# 468332_001_Inputs.net
KiCad netlist of a schematic drawn in Altium Designer
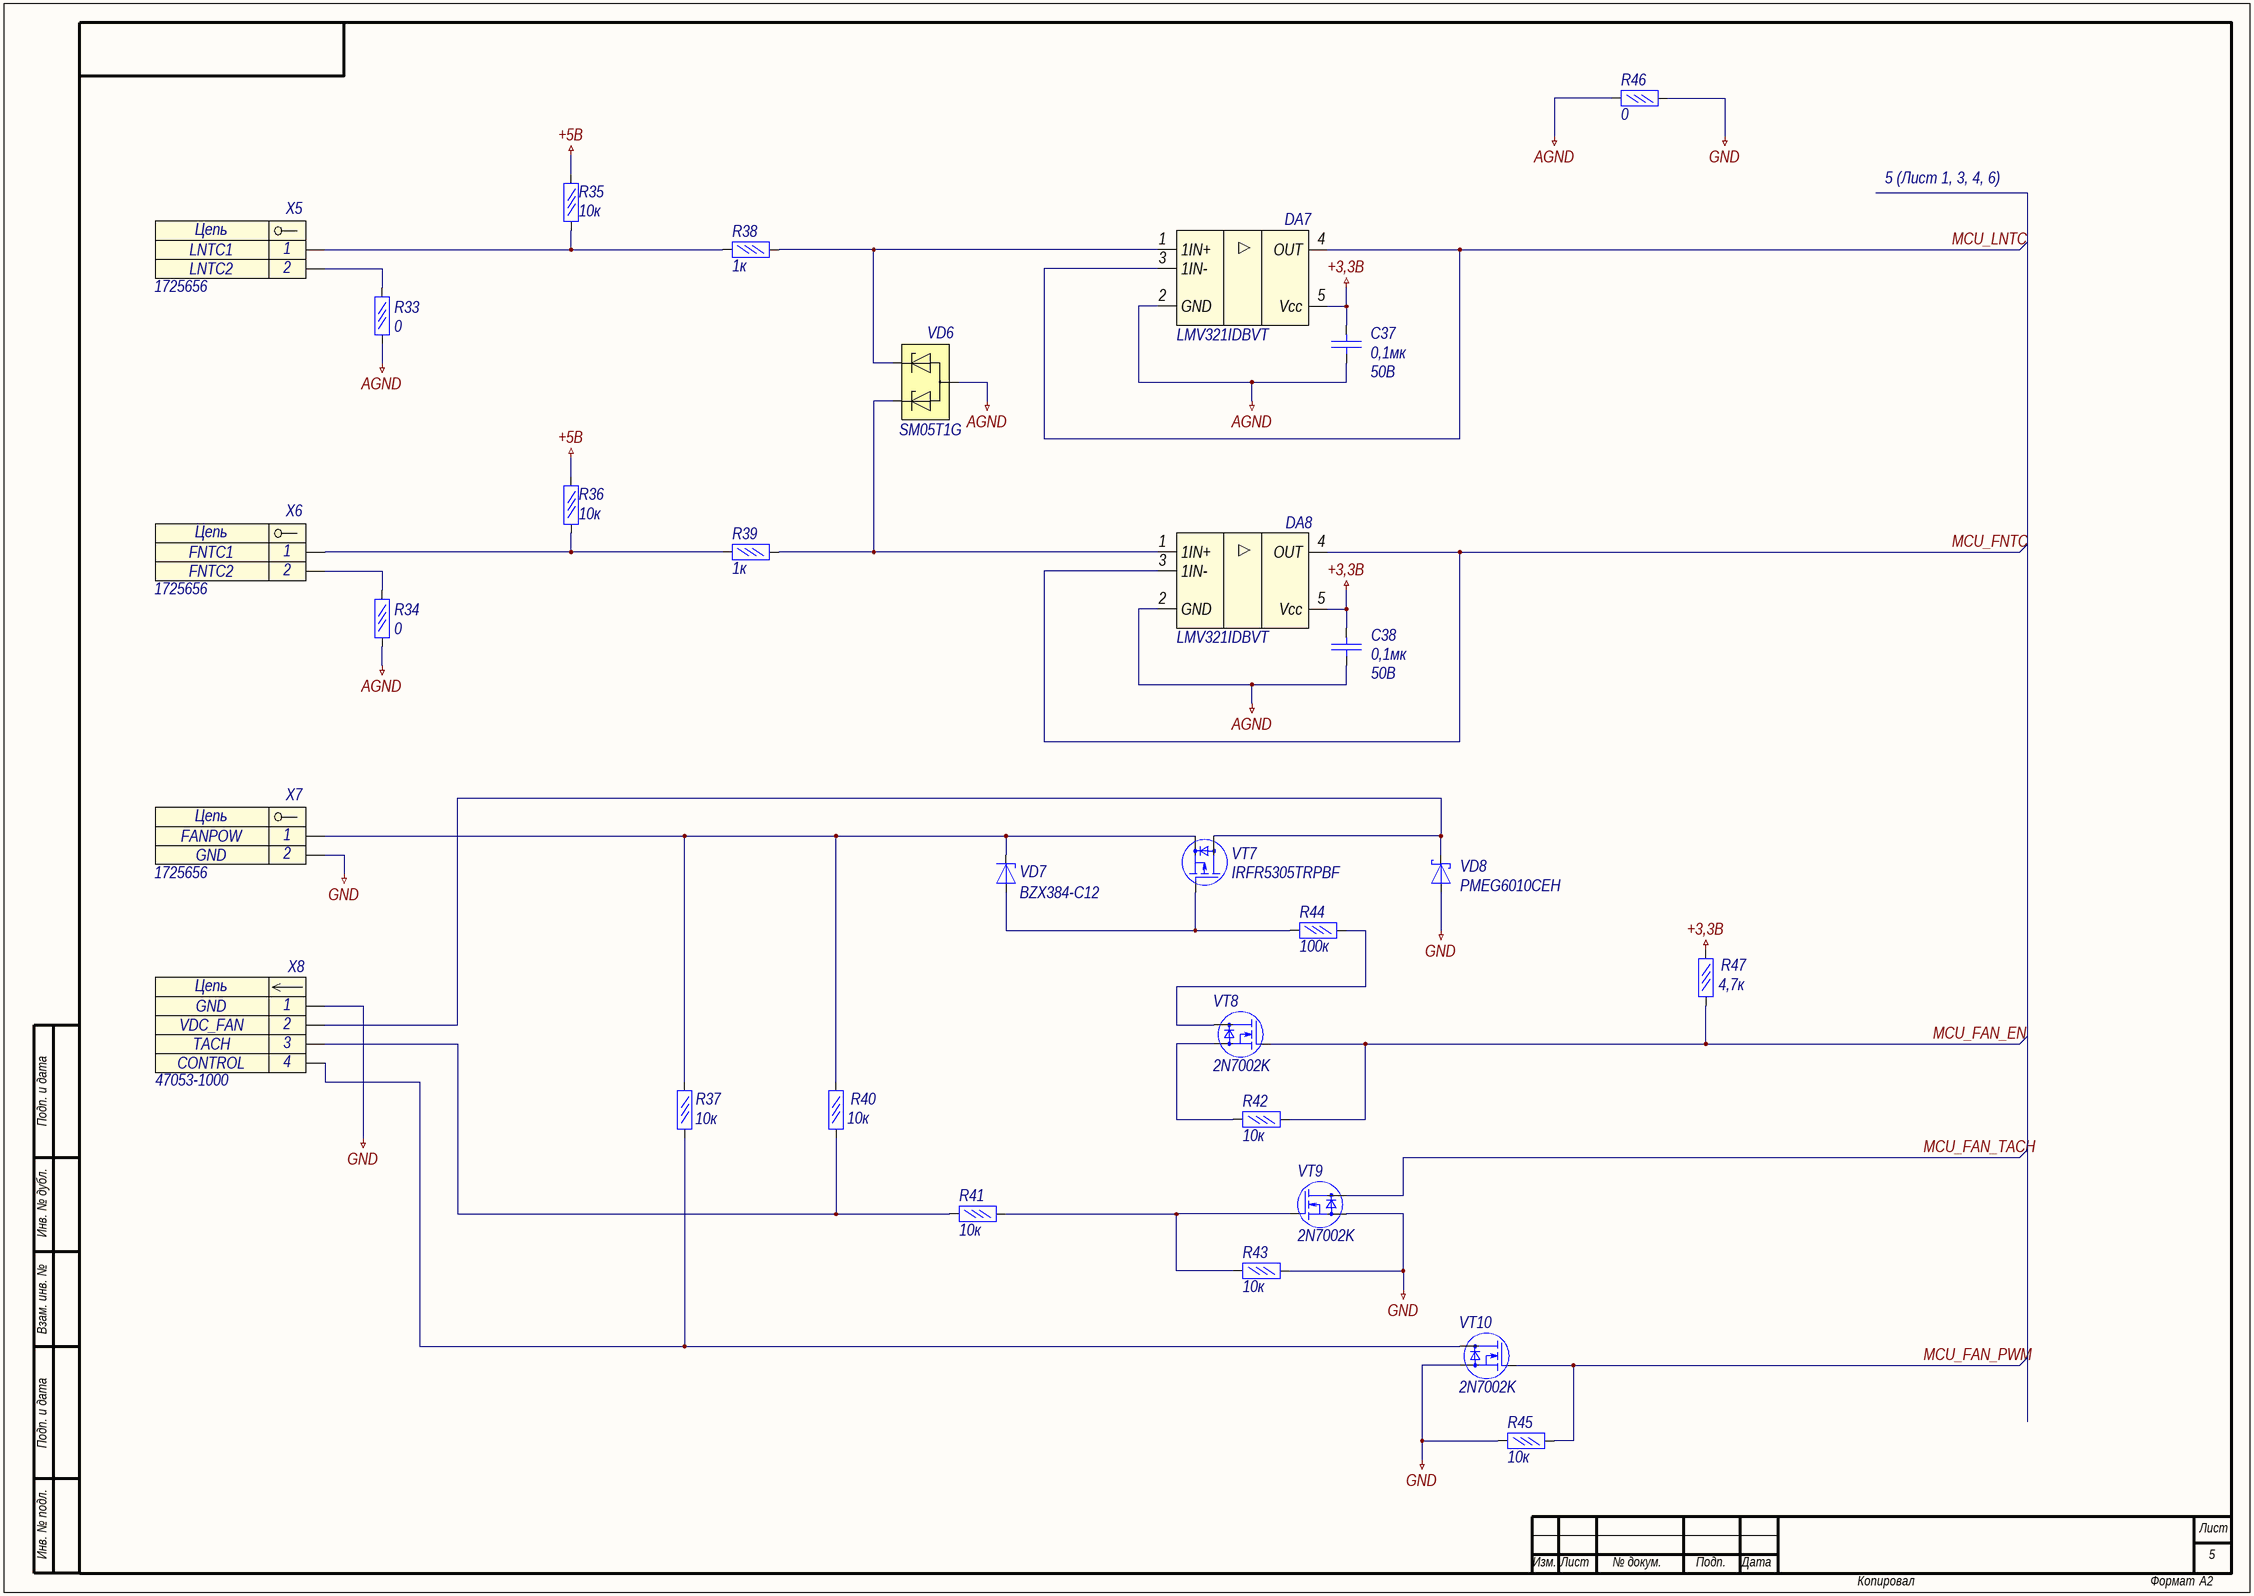
[diagram p0: РЕУН.468332.001_Inputs.SchDoc]

(export (version "E")
  (design (tool "Eeschema 10.0.6"))
  (components
    (comp (ref "C37")
      (value "0,1мк")
      (footprint "C0805_AA")
      (description "Конденсатор кер.")
      (fields (field (name "VOLTAGE") "50В"))
      (libsource (lib "Library_Diana") (part "Конденсатор кер."))
    )
    (comp (ref "C38")
      (value "0,1мк")
      (footprint "C0805_AA")
      (description "Конденсатор кер.")
      (fields (field (name "VOLTAGE") "50В"))
      (libsource (lib "Library_Diana") (part "Конденсатор кер."))
    )
    (comp (ref "DA7")
      (value "LMV321IDBVT")
      (description "Операционный усилитель Rail-to-rail")
      (libsource (lib "Library_Diana") (part "LMV321"))
    )
    (comp (ref "DA8")
      (value "LMV321IDBVT")
      (description "Операционный усилитель Rail-to-rail")
      (libsource (lib "Library_Diana") (part "LMV321"))
    )
    (comp (ref "R33")
      (value "0")
      (footprint "R1206")
      (description "Резистор 0,05Вт")
      (libsource (lib "Library_Diana") (part "Резистор  0,05Вт"))
    )
    (comp (ref "R34")
      (value "0")
      (footprint "R1206")
      (description "Резистор 0,05Вт")
      (libsource (lib "Library_Diana") (part "Резистор  0,05Вт"))
    )
    (comp (ref "R35")
      (value "10к")
      (footprint "R1206")
      (description "Резистор 0,05Вт")
      (libsource (lib "Library_Diana") (part "Резистор  0,05Вт"))
    )
    (comp (ref "R36")
      (value "10к")
      (footprint "R1206")
      (description "Резистор 0,05Вт")
      (libsource (lib "Library_Diana") (part "Резистор  0,05Вт"))
    )
    (comp (ref "R37")
      (value "10к")
      (footprint "R1206")
      (description "Резистор 0,05Вт")
      (libsource (lib "Library_Diana") (part "Резистор  0,05Вт"))
    )
    (comp (ref "R38")
      (value "1к")
      (footprint "R1206")
      (description "Резистор 0,05Вт")
      (libsource (lib "") (part "Резистор  0,05Вт_2"))
    )
    (comp (ref "R39")
      (value "1к")
      (footprint "R1206")
      (description "Резистор 0,05Вт")
      (libsource (lib "") (part "Резистор  0,05Вт_2"))
    )
    (comp (ref "R40")
      (value "10к")
      (footprint "R1206")
      (description "Резистор 0,05Вт")
      (libsource (lib "Library_Diana") (part "Резистор  0,05Вт"))
    )
    (comp (ref "R41")
      (value "10к")
      (footprint "R1206")
      (description "Резистор 0,05Вт")
      (libsource (lib "") (part "Резистор  0,05Вт_2"))
    )
    (comp (ref "R42")
      (value "10к")
      (footprint "R1206")
      (description "Резистор 0,05Вт")
      (libsource (lib "") (part "Резистор  0,05Вт_1"))
    )
    (comp (ref "R43")
      (value "10к")
      (footprint "R1206")
      (description "Резистор 0,05Вт")
      (libsource (lib "") (part "Резистор  0,05Вт_1"))
    )
    (comp (ref "R44")
      (value "100к")
      (footprint "R1206")
      (description "Резистор 0,05Вт")
      (libsource (lib "") (part "Резистор  0,05Вт_2"))
    )
    (comp (ref "R45")
      (value "10к")
      (footprint "R1206")
      (description "Резистор 0,05Вт")
      (libsource (lib "") (part "Резистор  0,05Вт_1"))
    )
    (comp (ref "R46")
      (value "0")
      (footprint "R1206")
      (description "Резистор 0,05Вт")
      (libsource (lib "") (part "Резистор  0,05Вт_1"))
    )
    (comp (ref "R47")
      (value "4,7к")
      (footprint "R1206")
      (description "Резистор 0,05Вт")
      (libsource (lib "Library_Diana") (part "Резистор  0,05Вт"))
    )
    (comp (ref "VD6")
      (value "SM05T1G")
      (description "Сборка TVS-диодов")
      (libsource (lib "Library_Diana") (part "ZenerArray2"))
    )
    (comp (ref "VD7")
      (value "BZX384-C12")
      (footprint "SOT23-2_A")
      (description "Стабилитрон")
      (libsource (lib "Library_Diana") (part "DiodeZener"))
    )
    (comp (ref "VD8")
      (value "PMEG6010CEH")
      (footprint "SOD123_A")
      (description "Диод Шоттки")
      (libsource (lib "Library_Diana") (part "DiodeSchottky"))
    )
    (comp (ref "VT7")
      (value "IRFR5305TRPBF")
      (description "Полевой P-канальный транзистор")
      (fields (field (name "NAME") "IRFR5305TRPBF"))
      (libsource (lib "Library_Diana") (part "mosfet-p-1-3-2"))
    )
    (comp (ref "VT8")
      (value "2N7002K")
      (footprint "SOT:SOT23-3")
      (fields (field (name "NAME") "2N7002K"))
      (libsource (lib "Library_Diana") (part "mosfet-n"))
    )
    (comp (ref "VT9")
      (value "2N7002K")
      (footprint "SOT:SOT23-3")
      (fields (field (name "NAME") "2N7002K"))
      (libsource (lib "Library_Diana") (part "mosfet-n"))
    )
    (comp (ref "VT10")
      (value "2N7002K")
      (footprint "SOT:SOT23-3")
      (fields (field (name "NAME") "2N7002K"))
      (libsource (lib "Library_Diana") (part "mosfet-n"))
    )
    (comp (ref "X5")
      (value "1725656")
      (description "Разъем - 1 конт. клемма")
      (fields (field (name "NAME") "1725656"))
      (libsource (lib "Library_Diana") (part "x1-k_1"))
    )
    (comp (ref "X6")
      (value "1725656")
      (description "Разъем - 1 конт. клемма")
      (fields (field (name "NAME") "1725656"))
      (libsource (lib "Library_Diana") (part "x1-k_1"))
    )
    (comp (ref "X7")
      (value "1725656")
      (description "Разъем - 1 конт. клемма")
      (fields (field (name "NAME") "1725656"))
      (libsource (lib "Library_Diana") (part "x1-k_1"))
    )
    (comp (ref "X8")
      (value "47053-1000")
      (description "Разъем - 10 конт. вилка")
      (fields (field (name "NAME") "47053-1000"))
      (libsource (lib "Library_Diana") (part "x10-m_1"))
    )
  )
  (nets
    (net (code "1") (name "+3,3В") (class "Default")
      (node (ref "C37") (pin "2") (pinfunction "2_2") (pintype "passive"))
      (node (ref "C38") (pin "2") (pinfunction "2_2") (pintype "passive"))
      (node (ref "DA7") (pin "5") (pinfunction "Vcc_5") (pintype "passive"))
      (node (ref "DA8") (pin "5") (pinfunction "Vcc_5") (pintype "passive"))
      (node (ref "R47") (pin "2") (pinfunction "2_2") (pintype "passive"))
    )
    (net (code "2") (name "+5В") (class "Default")
      (node (ref "R35") (pin "2") (pinfunction "2_2") (pintype "passive"))
      (node (ref "R36") (pin "2") (pinfunction "2_2") (pintype "passive"))
    )
    (net (code "3") (name "/MCU_FAN_EN") (class "Default")
      (node (ref "R42") (pin "1") (pinfunction "1_1") (pintype "passive"))
      (node (ref "R47") (pin "1") (pinfunction "1_1") (pintype "passive"))
      (node (ref "VT8") (pin "1") (pinfunction "G_1") (pintype "passive"))
    )
    (net (code "4") (name "/MCU_FAN_PWM") (class "Default")
      (node (ref "R45") (pin "1") (pinfunction "1_1") (pintype "passive"))
      (node (ref "VT10") (pin "1") (pinfunction "G_1") (pintype "passive"))
    )
    (net (code "5") (name "/MCU_FAN_TACH") (class "Default")
      (node (ref "VT9") (pin "3") (pinfunction "D_3") (pintype "passive"))
    )
    (net (code "6") (name "/MCU_FNTC") (class "Default")
      (node (ref "DA8") (pin "3") (pinfunction "1IN-_3") (pintype "passive"))
      (node (ref "DA8") (pin "4") (pinfunction "OUT_4") (pintype "passive"))
    )
    (net (code "7") (name "/MCU_LNTC") (class "Default")
      (node (ref "DA7") (pin "3") (pinfunction "1IN-_3") (pintype "passive"))
      (node (ref "DA7") (pin "4") (pinfunction "OUT_4") (pintype "passive"))
    )
    (net (code "8") (name "AGND") (class "Default")
      (node (ref "C37") (pin "1") (pinfunction "1_1") (pintype "passive"))
      (node (ref "C38") (pin "1") (pinfunction "1_1") (pintype "passive"))
      (node (ref "DA7") (pin "2") (pinfunction "GND_2") (pintype "passive"))
      (node (ref "DA8") (pin "2") (pinfunction "GND_2") (pintype "passive"))
      (node (ref "R33") (pin "1") (pinfunction "1_1") (pintype "passive"))
      (node (ref "R34") (pin "1") (pinfunction "1_1") (pintype "passive"))
      (node (ref "R46") (pin "2") (pinfunction "2_2") (pintype "passive"))
      (node (ref "VD6") (pin "3") (pintype "passive"))
    )
    (net (code "9") (name "GND") (class "Default")
      (node (ref "R43") (pin "1") (pinfunction "1_1") (pintype "passive"))
      (node (ref "R45") (pin "2") (pinfunction "2_2") (pintype "passive"))
      (node (ref "R46") (pin "1") (pinfunction "1_1") (pintype "passive"))
      (node (ref "VD8") (pin "2") (pinfunction "A_2") (pintype "passive"))
      (node (ref "VT10") (pin "2") (pinfunction "S_2") (pintype "passive"))
      (node (ref "VT9") (pin "2") (pinfunction "S_2") (pintype "passive"))
      (node (ref "X7") (pin "2") (pinfunction "2_2") (pintype "passive"))
      (node (ref "X8") (pin "1") (pinfunction "1_1") (pintype "passive"))
    )
    (net (code "10") (name "Net-(DA7-1IN+)") (class "Default")
      (node (ref "DA7") (pin "1") (pinfunction "1IN+_1") (pintype "passive"))
      (node (ref "R38") (pin "2") (pinfunction "2_2") (pintype "passive"))
      (node (ref "VD6") (pin "2") (pintype "passive"))
    )
    (net (code "11") (name "Net-(DA8-1IN+)") (class "Default")
      (node (ref "DA8") (pin "1") (pinfunction "1IN+_1") (pintype "passive"))
      (node (ref "R39") (pin "2") (pinfunction "2_2") (pintype "passive"))
      (node (ref "VD6") (pin "1") (pintype "passive"))
    )
    (net (code "12") (name "Net-(R33-Pad2)") (class "Default")
      (node (ref "R33") (pin "2") (pinfunction "2_2") (pintype "passive"))
      (node (ref "X5") (pin "2") (pinfunction "2_2") (pintype "passive"))
    )
    (net (code "13") (name "Net-(R34-Pad2)") (class "Default")
      (node (ref "R34") (pin "2") (pinfunction "2_2") (pintype "passive"))
      (node (ref "X6") (pin "2") (pinfunction "2_2") (pintype "passive"))
    )
    (net (code "14") (name "Net-(R35-Pad1)") (class "Default")
      (node (ref "R35") (pin "1") (pinfunction "1_1") (pintype "passive"))
      (node (ref "R38") (pin "1") (pinfunction "1_1") (pintype "passive"))
      (node (ref "X5") (pin "1") (pinfunction "1_1") (pintype "passive"))
    )
    (net (code "15") (name "Net-(R36-Pad1)") (class "Default")
      (node (ref "R36") (pin "1") (pinfunction "1_1") (pintype "passive"))
      (node (ref "R39") (pin "1") (pinfunction "1_1") (pintype "passive"))
      (node (ref "X6") (pin "1") (pinfunction "1_1") (pintype "passive"))
    )
    (net (code "16") (name "Net-(R40-Pad1)") (class "Default")
      (node (ref "R40") (pin "1") (pinfunction "1_1") (pintype "passive"))
      (node (ref "R41") (pin "1") (pinfunction "1_1") (pintype "passive"))
      (node (ref "X8") (pin "3") (pinfunction "3_3") (pintype "passive"))
    )
    (net (code "17") (name "Net-(VD7-A)") (class "Default")
      (node (ref "R44") (pin "1") (pinfunction "1_1") (pintype "passive"))
      (node (ref "VD7") (pin "2") (pinfunction "A_2") (pintype "passive"))
      (node (ref "VT7") (pin "1") (pinfunction "G_1") (pintype "passive"))
    )
    (net (code "18") (name "Net-(VD7-K)") (class "Default")
      (node (ref "R37") (pin "2") (pinfunction "2_2") (pintype "passive"))
      (node (ref "R40") (pin "2") (pinfunction "2_2") (pintype "passive"))
      (node (ref "VD7") (pin "1") (pinfunction "K_1") (pintype "passive"))
      (node (ref "VT7") (pin "2") (pinfunction "S_2") (pintype "passive"))
      (node (ref "X7") (pin "1") (pinfunction "1_1") (pintype "passive"))
    )
    (net (code "19") (name "Net-(VD8-K)") (class "Default")
      (node (ref "VD8") (pin "1") (pinfunction "K_1") (pintype "passive"))
      (node (ref "VT7") (pin "3") (pinfunction "D_3") (pintype "passive"))
      (node (ref "X8") (pin "2") (pinfunction "2_2") (pintype "passive"))
    )
    (net (code "20") (name "Net-(VT8-D)") (class "Default")
      (node (ref "R44") (pin "2") (pinfunction "2_2") (pintype "passive"))
      (node (ref "VT8") (pin "3") (pinfunction "D_3") (pintype "passive"))
    )
    (net (code "21") (name "Net-(VT8-S)") (class "Default")
      (node (ref "R42") (pin "2") (pinfunction "2_2") (pintype "passive"))
      (node (ref "VT8") (pin "2") (pinfunction "S_2") (pintype "passive"))
    )
    (net (code "22") (name "Net-(VT9-G)") (class "Default")
      (node (ref "R41") (pin "2") (pinfunction "2_2") (pintype "passive"))
      (node (ref "R43") (pin "2") (pinfunction "2_2") (pintype "passive"))
      (node (ref "VT9") (pin "1") (pinfunction "G_1") (pintype "passive"))
    )
    (net (code "23") (name "Net-(VT10-D)") (class "Default")
      (node (ref "R37") (pin "1") (pinfunction "1_1") (pintype "passive"))
      (node (ref "VT10") (pin "3") (pinfunction "D_3") (pintype "passive"))
      (node (ref "X8") (pin "4") (pinfunction "4_4") (pintype "passive"))
    )
  )
)
